# Ethernet1.net
KiCad netlist of a schematic drawn in Altium Designer
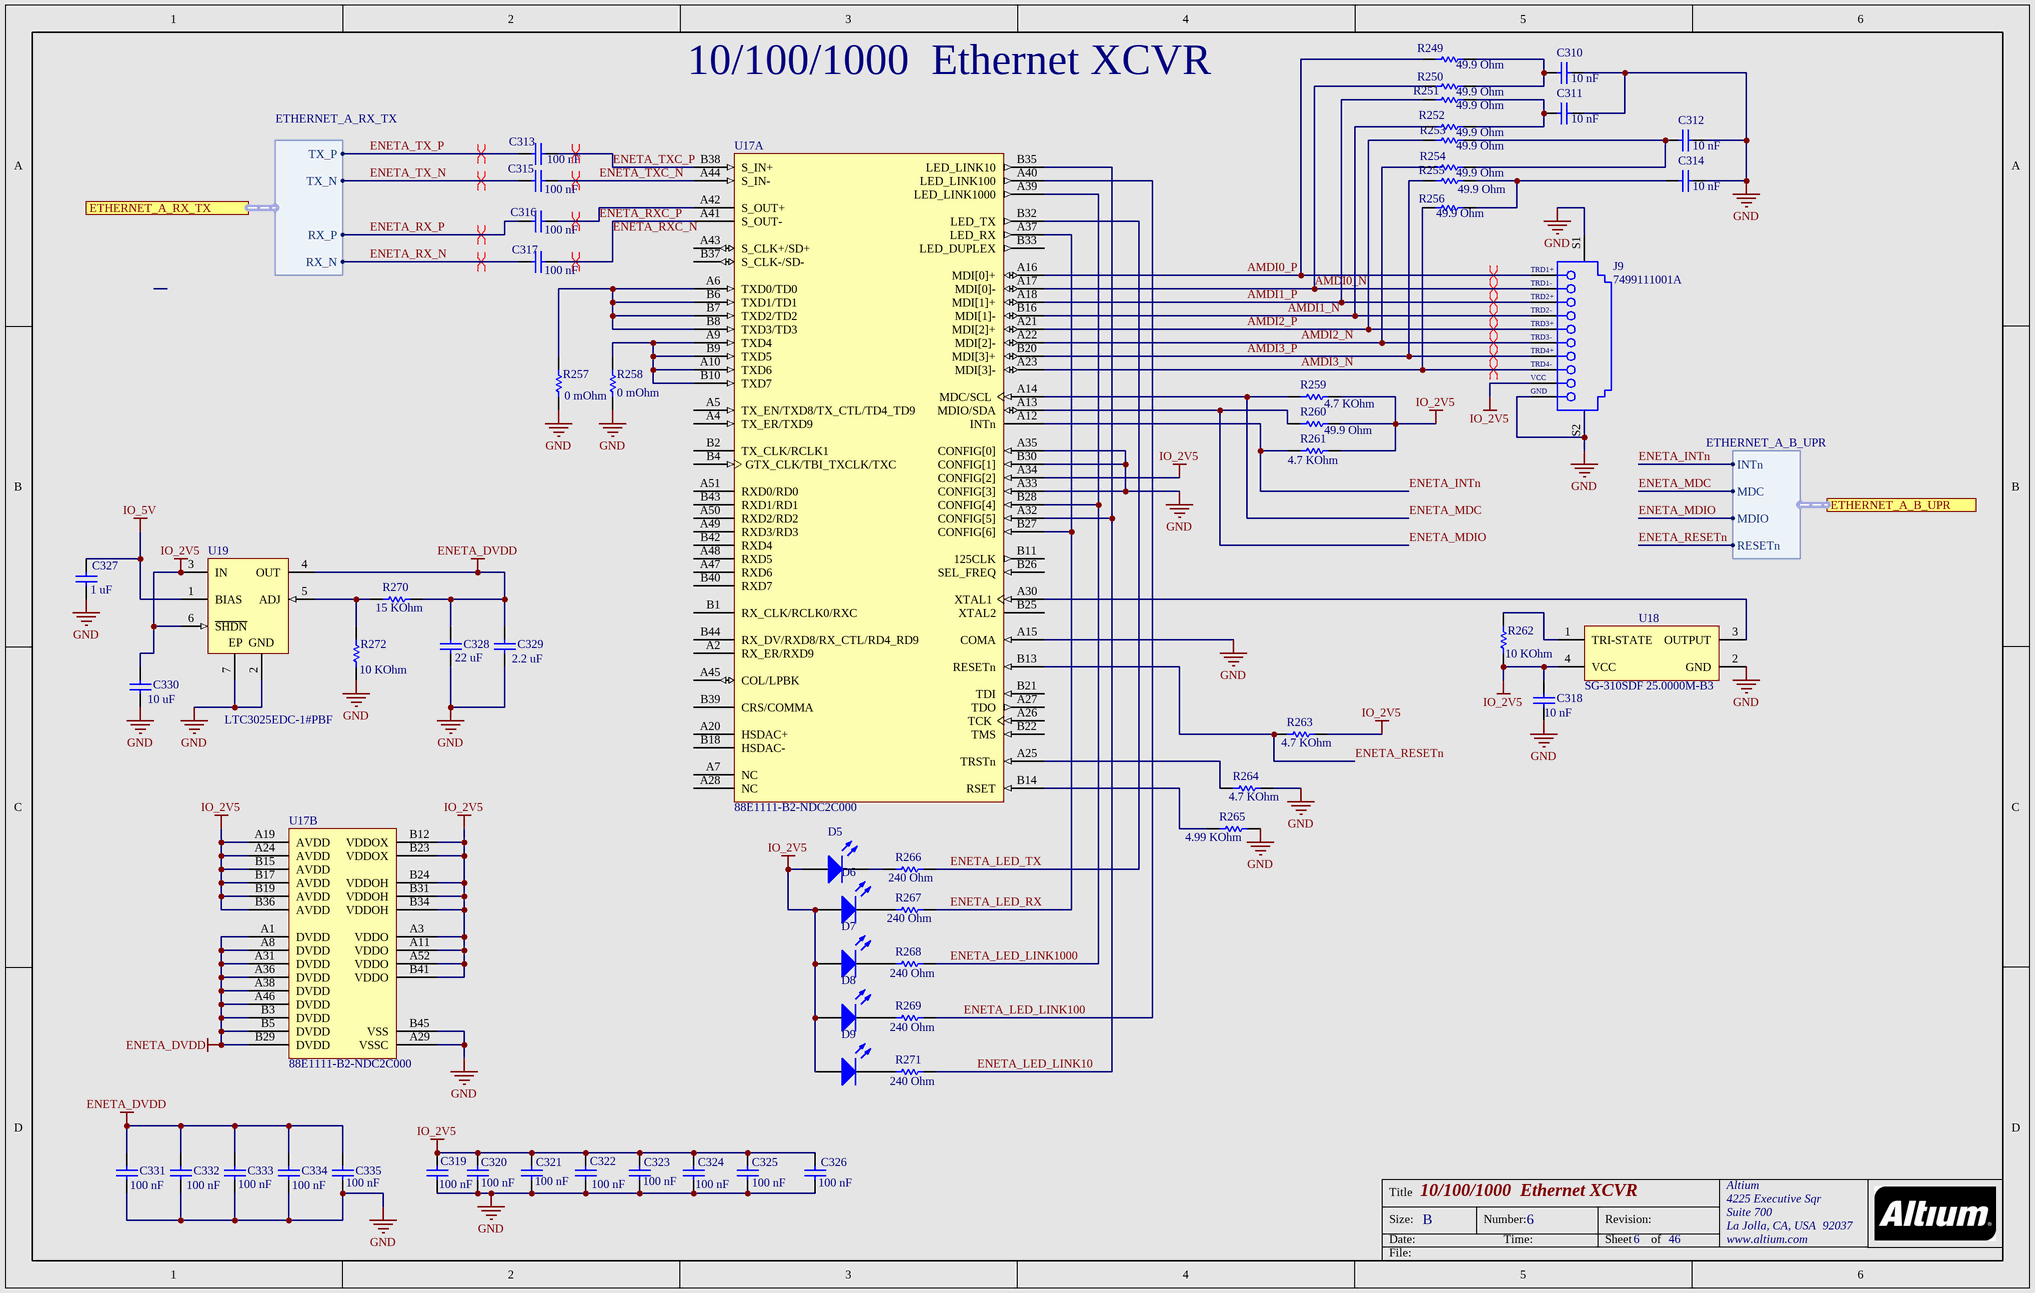
[diagram p0: Ethernet1.SchDoc]

(export (version "E")
  (design (tool "Eeschema 10.0.6"))
  (components
    (comp (ref "C310")
      (value "GRM155R71H103KA88D")
      (footprint "CAPC1005X55X25ML05T10")
      (description "Chip Capacitor, 10 nF, +/- 10%, 50 V, -55 to 125 degC, 0402 (1005 Metric), RoHS, Tape and Reel")
      (fields
        (field (name "TOLERANCE") "10%")
        (field (name "CAPACITANCE") "10 nF")
        (field (name "MANUFACTURER") "Basic Passives")
      )
      (libsource (lib "Altium Content Vault") (part "CAP-NP-2"))
    )
    (comp (ref "C311")
      (value "GRM155R71H103KA88D")
      (footprint "CAPC1005X55X25ML05T10")
      (description "Chip Capacitor, 10 nF, +/- 10%, 50 V, -55 to 125 degC, 0402 (1005 Metric), RoHS, Tape and Reel")
      (fields
        (field (name "TOLERANCE") "10%")
        (field (name "CAPACITANCE") "10 nF")
        (field (name "MANUFACTURER") "Basic Passives")
      )
      (libsource (lib "Altium Content Vault") (part "CAP-NP-2"))
    )
    (comp (ref "C312")
      (value "GRM155R71H103KA88D")
      (footprint "CAPC1005X55X25ML05T10")
      (description "Chip Capacitor, 10 nF, +/- 10%, 50 V, -55 to 125 degC, 0402 (1005 Metric), RoHS, Tape and Reel")
      (fields
        (field (name "TOLERANCE") "10%")
        (field (name "CAPACITANCE") "10 nF")
        (field (name "MANUFACTURER") "Basic Passives")
      )
      (libsource (lib "Altium Content Vault") (part "CAP-NP-2"))
    )
    (comp (ref "C313")
      (value "C1005X7R1E104M")
      (footprint "CAPC1005X55X10LL05")
      (description "Chip Capacitor, 0.1 uF, +/- 20%, 25 V, -55 to 125 degC, 0402 (1005 Metric), RoHS, Tape and Reel")
      (fields (field (name "TOLERANCE") "20%") (field (name "CAPACITANCE") "100 nF"))
      (libsource (lib "Altium Content Vault") (part "CAP-NP-2"))
    )
    (comp (ref "C314")
      (value "GRM155R71H103KA88D")
      (footprint "CAPC1005X55X25ML05T10")
      (description "Chip Capacitor, 10 nF, +/- 10%, 50 V, -55 to 125 degC, 0402 (1005 Metric), RoHS, Tape and Reel")
      (fields
        (field (name "TOLERANCE") "10%")
        (field (name "CAPACITANCE") "10 nF")
        (field (name "MANUFACTURER") "Basic Passives")
      )
      (libsource (lib "Altium Content Vault") (part "CAP-NP-2"))
    )
    (comp (ref "C315")
      (value "C1005X7R1E104M")
      (footprint "CAPC1005X55X10LL05")
      (description "Chip Capacitor, 0.1 uF, +/- 20%, 25 V, -55 to 125 degC, 0402 (1005 Metric), RoHS, Tape and Reel")
      (fields (field (name "TOLERANCE") "20%") (field (name "CAPACITANCE") "100 nF"))
      (libsource (lib "Altium Content Vault") (part "CAP-NP-2"))
    )
    (comp (ref "C316")
      (value "C1005X7R1E104M")
      (footprint "CAPC1005X55X10LL05")
      (description "Chip Capacitor, 0.1 uF, +/- 20%, 25 V, -55 to 125 degC, 0402 (1005 Metric), RoHS, Tape and Reel")
      (fields (field (name "TOLERANCE") "20%") (field (name "CAPACITANCE") "100 nF"))
      (libsource (lib "Altium Content Vault") (part "CAP-NP-2"))
    )
    (comp (ref "C317")
      (value "C1005X7R1E104M")
      (footprint "CAPC1005X55X10LL05")
      (description "Chip Capacitor, 0.1 uF, +/- 20%, 25 V, -55 to 125 degC, 0402 (1005 Metric), RoHS, Tape and Reel")
      (fields (field (name "TOLERANCE") "20%") (field (name "CAPACITANCE") "100 nF"))
      (libsource (lib "Altium Content Vault") (part "CAP-NP-2"))
    )
    (comp (ref "C318")
      (value "GRM155R71H103KA88D")
      (footprint "CAPC1005X55X25ML05T10")
      (description "Chip Capacitor, 10 nF, +/- 10%, 50 V, -55 to 125 degC, 0402 (1005 Metric), RoHS, Tape and Reel")
      (fields
        (field (name "TOLERANCE") "10%")
        (field (name "CAPACITANCE") "10 nF")
        (field (name "MANUFACTURER") "Basic Passives")
      )
      (libsource (lib "Altium Content Vault") (part "CAP-NP-2"))
    )
    (comp (ref "C319")
      (value "C1005X7R1E104M")
      (footprint "CAPC1005X55X10LL05")
      (description "Chip Capacitor, 0.1 uF, +/- 20%, 25 V, -55 to 125 degC, 0402 (1005 Metric), RoHS, Tape and Reel")
      (fields (field (name "TOLERANCE") "20%") (field (name "CAPACITANCE") "100 nF"))
      (libsource (lib "Altium Content Vault") (part "CAP-NP-2"))
    )
    (comp (ref "C320")
      (value "C1005X7R1E104M")
      (footprint "CAPC1005X55X10LL05")
      (description "Chip Capacitor, 0.1 uF, +/- 20%, 25 V, -55 to 125 degC, 0402 (1005 Metric), RoHS, Tape and Reel")
      (fields (field (name "TOLERANCE") "20%") (field (name "CAPACITANCE") "100 nF"))
      (libsource (lib "Altium Content Vault") (part "CAP-NP-2"))
    )
    (comp (ref "C321")
      (value "C1005X7R1E104M")
      (footprint "CAPC1005X55X10LL05")
      (description "Chip Capacitor, 0.1 uF, +/- 20%, 25 V, -55 to 125 degC, 0402 (1005 Metric), RoHS, Tape and Reel")
      (fields (field (name "TOLERANCE") "20%") (field (name "CAPACITANCE") "100 nF"))
      (libsource (lib "Altium Content Vault") (part "CAP-NP-2"))
    )
    (comp (ref "C322")
      (value "C1005X7R1E104M")
      (footprint "CAPC1005X55X10LL05")
      (description "Chip Capacitor, 0.1 uF, +/- 20%, 25 V, -55 to 125 degC, 0402 (1005 Metric), RoHS, Tape and Reel")
      (fields (field (name "TOLERANCE") "20%") (field (name "CAPACITANCE") "100 nF"))
      (libsource (lib "Altium Content Vault") (part "CAP-NP-2"))
    )
    (comp (ref "C323")
      (value "C1005X7R1E104M")
      (footprint "CAPC1005X55X10LL05")
      (description "Chip Capacitor, 0.1 uF, +/- 20%, 25 V, -55 to 125 degC, 0402 (1005 Metric), RoHS, Tape and Reel")
      (fields (field (name "TOLERANCE") "20%") (field (name "CAPACITANCE") "100 nF"))
      (libsource (lib "Altium Content Vault") (part "CAP-NP-2"))
    )
    (comp (ref "C324")
      (value "C1005X7R1E104M")
      (footprint "CAPC1005X55X10LL05")
      (description "Chip Capacitor, 0.1 uF, +/- 20%, 25 V, -55 to 125 degC, 0402 (1005 Metric), RoHS, Tape and Reel")
      (fields (field (name "TOLERANCE") "20%") (field (name "CAPACITANCE") "100 nF"))
      (libsource (lib "Altium Content Vault") (part "CAP-NP-2"))
    )
    (comp (ref "C325")
      (value "C1005X7R1E104M")
      (footprint "CAPC1005X55X10LL05")
      (description "Chip Capacitor, 0.1 uF, +/- 20%, 25 V, -55 to 125 degC, 0402 (1005 Metric), RoHS, Tape and Reel")
      (fields (field (name "TOLERANCE") "20%") (field (name "CAPACITANCE") "100 nF"))
      (libsource (lib "Altium Content Vault") (part "CAP-NP-2"))
    )
    (comp (ref "C326")
      (value "C1005X7R1E104M")
      (footprint "CAPC1005X55X10LL05")
      (description "Chip Capacitor, 0.1 uF, +/- 20%, 25 V, -55 to 125 degC, 0402 (1005 Metric), RoHS, Tape and Reel")
      (fields (field (name "TOLERANCE") "20%") (field (name "CAPACITANCE") "100 nF"))
      (libsource (lib "Altium Content Vault") (part "CAP-NP-2"))
    )
    (comp (ref "C327")
      (value "CGB2A1X5R1E105K033BC")
      (footprint "CAPC1005X33X10LL5")
      (description "Chip Capacitor, 1 uF, +/- 10%, 25 V, -55 to 85 degC, 0402 (1005 Metric), RoHS, Tape and Reel")
      (fields (field (name "CAPACITANCE") "1 uF") (field (name "TOLERANCE") "10%"))
      (libsource (lib "") (part "CAP-NP-2_1"))
    )
    (comp (ref "C328")
      (value "GRM31CR61E226KE15L")
      (footprint "CAPC3216X180X55ML20T25")
      (description "Chip Capacitor, 22 uF, +/- 10%, 25 V, -55 to 85 degC, 1206 (3216 Metric), RoHS, Tape and Reel")
      (fields (field (name "TOLERANCE") "10%") (field (name "CAPACITANCE") "22 uF"))
      (libsource (lib "Altium Content Vault") (part "CAP-NP-2"))
    )
    (comp (ref "C329")
      (value "GRM188R61A225KE34x")
      (footprint "CAPC1608X90X35ML10T15")
      (description "Chip Capacitor, 2.2 uF, +/- 10%, 10 V, -55 to 85 degC, 0603 (1608 Metric), RoHS, Tape and Reel")
      (fields (field (name "TOLERANCE") "10%") (field (name "CAPACITANCE") "2.2 uF"))
      (libsource (lib "Altium Content Vault") (part "CMP-1662-00016-2"))
    )
    (comp (ref "C330")
      (value "C2012X5R1C106K085AC")
      (footprint "CAPC2013X100X20NL20")
      (description "Chip Capacitor, 10 uF, +/- 10%, 16 V, -55 to 85 degC, 0805 (2012 Metric), RoHS, Tape and Reel")
      (fields (field (name "TOLERANCE") "10%") (field (name "CAPACITANCE") "10 uF"))
      (libsource (lib "Altium Content Vault") (part "CMP-1663-00007-1"))
    )
    (comp (ref "C331")
      (value "C1005X7R1E104M")
      (footprint "CAPC1005X55X10LL05")
      (description "Chip Capacitor, 0.1 uF, +/- 20%, 25 V, -55 to 125 degC, 0402 (1005 Metric), RoHS, Tape and Reel")
      (fields (field (name "TOLERANCE") "20%") (field (name "CAPACITANCE") "100 nF"))
      (libsource (lib "Altium Content Vault") (part "CAP-NP-2"))
    )
    (comp (ref "C332")
      (value "C1005X7R1E104M")
      (footprint "CAPC1005X55X10LL05")
      (description "Chip Capacitor, 0.1 uF, +/- 20%, 25 V, -55 to 125 degC, 0402 (1005 Metric), RoHS, Tape and Reel")
      (fields (field (name "TOLERANCE") "20%") (field (name "CAPACITANCE") "100 nF"))
      (libsource (lib "Altium Content Vault") (part "CAP-NP-2"))
    )
    (comp (ref "C333")
      (value "C1005X7R1E104M")
      (footprint "CAPC1005X55X10LL05")
      (description "Chip Capacitor, 0.1 uF, +/- 20%, 25 V, -55 to 125 degC, 0402 (1005 Metric), RoHS, Tape and Reel")
      (fields (field (name "TOLERANCE") "20%") (field (name "CAPACITANCE") "100 nF"))
      (libsource (lib "Altium Content Vault") (part "CAP-NP-2"))
    )
    (comp (ref "C334")
      (value "C1005X7R1E104M")
      (footprint "CAPC1005X55X10LL05")
      (description "Chip Capacitor, 0.1 uF, +/- 20%, 25 V, -55 to 125 degC, 0402 (1005 Metric), RoHS, Tape and Reel")
      (fields (field (name "TOLERANCE") "20%") (field (name "CAPACITANCE") "100 nF"))
      (libsource (lib "Altium Content Vault") (part "CAP-NP-2"))
    )
    (comp (ref "C335")
      (value "C1005X7R1E104M")
      (footprint "CAPC1005X55X10LL05")
      (description "Chip Capacitor, 0.1 uF, +/- 20%, 25 V, -55 to 125 degC, 0402 (1005 Metric), RoHS, Tape and Reel")
      (fields (field (name "TOLERANCE") "20%") (field (name "CAPACITANCE") "100 nF"))
      (libsource (lib "Altium Content Vault") (part "CAP-NP-2"))
    )
    (comp (ref "D5")
      (value "150060VS75000")
      (footprint "0603_A")
      (description "SMD mono-color Chip LED, WL-SMCW, Bright Green")
      (fields (field (name "MANUFACTURER") "Wuerth Elektronik"))
      (libsource (lib "Altium Content Vault") (part "CMP-1426-00006-1"))
    )
    (comp (ref "D6")
      (value "150060VS75000")
      (footprint "0603_A")
      (description "SMD mono-color Chip LED, WL-SMCW, Bright Green")
      (fields (field (name "MANUFACTURER") "Wuerth Elektronik"))
      (libsource (lib "Altium Content Vault") (part "CMP-1426-00006-1"))
    )
    (comp (ref "D7")
      (value "150060VS75000")
      (footprint "0603_A")
      (description "SMD mono-color Chip LED, WL-SMCW, Bright Green")
      (fields (field (name "MANUFACTURER") "Wuerth Elektronik"))
      (libsource (lib "Altium Content Vault") (part "CMP-1426-00006-1"))
    )
    (comp (ref "D8")
      (value "150060VS75000")
      (footprint "0603_A")
      (description "SMD mono-color Chip LED, WL-SMCW, Bright Green")
      (fields (field (name "MANUFACTURER") "Wuerth Elektronik"))
      (libsource (lib "Altium Content Vault") (part "CMP-1426-00006-1"))
    )
    (comp (ref "D9")
      (value "150060VS75000")
      (footprint "0603_A")
      (description "SMD mono-color Chip LED, WL-SMCW, Bright Green")
      (fields (field (name "MANUFACTURER") "Wuerth Elektronik"))
      (libsource (lib "Altium Content Vault") (part "CMP-1426-00006-1"))
    )
    (comp (ref "J9")
      (value "7499111001A")
      (footprint "WE-7499111001A_V")
      (description "RJ45 LAN Transformer, Modular JACK, 0 to 70 degC, 10-Pin THD, RoHS, Tube")
      (libsource (lib "Altium Content Vault") (part "RJ45-10-2SHLD_A"))
    )
    (comp (ref "R249")
      (value "NRC04F49R9TRF")
      (footprint "RESC1005X35X25NL8T10")
      (description "Chip Resistor, 49.9 Ohm, +/- 1%, 0.06 W, -55 to 155 degC, 0402 (1005 Metric), RoHS, Tape and Reel")
      (fields (field (name "TOLERANCE") "1%") (field (name "RESISTANCE") "49.9 Ohm"))
      (libsource (lib "Altium Content Vault") (part "RES-2"))
    )
    (comp (ref "R250")
      (value "NRC04F49R9TRF")
      (footprint "RESC1005X35X25NL8T10")
      (description "Chip Resistor, 49.9 Ohm, +/- 1%, 0.06 W, -55 to 155 degC, 0402 (1005 Metric), RoHS, Tape and Reel")
      (fields (field (name "TOLERANCE") "1%") (field (name "RESISTANCE") "49.9 Ohm"))
      (libsource (lib "Altium Content Vault") (part "CMP-1599-00001-2"))
    )
    (comp (ref "R251")
      (value "NRC04F49R9TRF")
      (footprint "RESC1005X35X25NL8T10")
      (description "Chip Resistor, 49.9 Ohm, +/- 1%, 0.06 W, -55 to 155 degC, 0402 (1005 Metric), RoHS, Tape and Reel")
      (fields (field (name "TOLERANCE") "1%") (field (name "RESISTANCE") "49.9 Ohm"))
      (libsource (lib "Altium Content Vault") (part "CMP-1599-00001-2"))
    )
    (comp (ref "R252")
      (value "NRC04F49R9TRF")
      (footprint "RESC1005X35X25NL8T10")
      (description "Chip Resistor, 49.9 Ohm, +/- 1%, 0.06 W, -55 to 155 degC, 0402 (1005 Metric), RoHS, Tape and Reel")
      (fields (field (name "TOLERANCE") "1%") (field (name "RESISTANCE") "49.9 Ohm"))
      (libsource (lib "Altium Content Vault") (part "RES-2"))
    )
    (comp (ref "R253")
      (value "NRC04F49R9TRF")
      (footprint "RESC1005X35X25NL8T10")
      (description "Chip Resistor, 49.9 Ohm, +/- 1%, 0.06 W, -55 to 155 degC, 0402 (1005 Metric), RoHS, Tape and Reel")
      (fields (field (name "TOLERANCE") "1%") (field (name "RESISTANCE") "49.9 Ohm"))
      (libsource (lib "Altium Content Vault") (part "CMP-1599-00001-2"))
    )
    (comp (ref "R254")
      (value "NRC04F49R9TRF")
      (footprint "RESC1005X35X25NL8T10")
      (description "Chip Resistor, 49.9 Ohm, +/- 1%, 0.06 W, -55 to 155 degC, 0402 (1005 Metric), RoHS, Tape and Reel")
      (fields (field (name "TOLERANCE") "1%") (field (name "RESISTANCE") "49.9 Ohm"))
      (libsource (lib "Altium Content Vault") (part "CMP-1599-00001-2"))
    )
    (comp (ref "R255")
      (value "NRC04F49R9TRF")
      (footprint "RESC1005X35X25NL8T10")
      (description "Chip Resistor, 49.9 Ohm, +/- 1%, 0.06 W, -55 to 155 degC, 0402 (1005 Metric), RoHS, Tape and Reel")
      (fields (field (name "TOLERANCE") "1%") (field (name "RESISTANCE") "49.9 Ohm"))
      (libsource (lib "Altium Content Vault") (part "RES-2"))
    )
    (comp (ref "R256")
      (value "NRC04F49R9TRF")
      (footprint "RESC1005X35X25NL8T10")
      (description "Chip Resistor, 49.9 Ohm, +/- 1%, 0.06 W, -55 to 155 degC, 0402 (1005 Metric), RoHS, Tape and Reel")
      (fields (field (name "TOLERANCE") "1%") (field (name "RESISTANCE") "49.9 Ohm"))
      (libsource (lib "Altium Content Vault") (part "CMP-1599-00001-2"))
    )
    (comp (ref "R257")
      (value "ERJ-2GE0R00X")
      (footprint "RESC1005X40X25ML05T05")
      (description "Chip Resistor, 0 mOhm, +/- 5%, 100 mW, -55 to 155 degC, 0402 (1005 Metric), RoHS, Tape and Reel")
      (fields
        (field (name "TOLERANCE") "5%")
        (field (name "RESISTANCE") "0 mOhm")
        (field (name "MANUFACTURER") "Basic Passives")
      )
      (libsource (lib "Altium Content Vault") (part "RES-2"))
    )
    (comp (ref "R258")
      (value "ERJ-2GE0R00X")
      (footprint "RESC1005X40X25ML05T05")
      (description "Chip Resistor, 0 mOhm, +/- 5%, 100 mW, -55 to 155 degC, 0402 (1005 Metric), RoHS, Tape and Reel")
      (fields
        (field (name "TOLERANCE") "5%")
        (field (name "RESISTANCE") "0 mOhm")
        (field (name "MANUFACTURER") "Basic Passives")
      )
      (libsource (lib "Altium Content Vault") (part "RES-2"))
    )
    (comp (ref "R259")
      (value "ERJ-2RKF4701X")
      (footprint "RESC1005X40X25LL05T05")
      (description "Chip Resistor, 4.7 KOhm, +/- 1%, 0.1 W, -55 to 155 degC, 0402 (1005 Metric), RoHS, Tape and Reel")
      (fields (field (name "TOLERANCE") "1%") (field (name "RESISTANCE") "4.7 KOhm"))
      (libsource (lib "Altium Content Vault") (part "RES-2"))
    )
    (comp (ref "R260")
      (value "NRC04F49R9TRF")
      (footprint "RESC1005X35X25NL8T10")
      (description "Chip Resistor, 49.9 Ohm, +/- 1%, 0.06 W, -55 to 155 degC, 0402 (1005 Metric), RoHS, Tape and Reel")
      (fields (field (name "TOLERANCE") "1%") (field (name "RESISTANCE") "49.9 Ohm"))
      (libsource (lib "Altium Content Vault") (part "RES-2"))
    )
    (comp (ref "R261")
      (value "ERJ-2RKF4701X")
      (footprint "RESC1005X40X25LL05T05")
      (description "Chip Resistor, 4.7 KOhm, +/- 1%, 0.1 W, -55 to 155 degC, 0402 (1005 Metric), RoHS, Tape and Reel")
      (fields (field (name "TOLERANCE") "1%") (field (name "RESISTANCE") "4.7 KOhm"))
      (libsource (lib "Altium Content Vault") (part "RES-2"))
    )
    (comp (ref "R262")
      (value "ERJ-2RKF1002X")
      (footprint "RESC1005X40X25NL05T05")
      (description "Chip Resistor, 10 KOhm, +/- 1%, 100 mW, -55 to 155 degC, 0402 (1005 Metric), RoHS, Tape and Reel")
      (fields
        (field (name "TOLERANCE") "1%")
        (field (name "RESISTANCE") "10 KOhm")
        (field (name "MANUFACTURER") "Basic Passives")
      )
      (libsource (lib "Altium Content Vault") (part "RES-2"))
    )
    (comp (ref "R263")
      (value "ERJ-2RKF4701X")
      (footprint "RESC1005X40X25LL05T05")
      (description "Chip Resistor, 4.7 KOhm, +/- 1%, 0.1 W, -55 to 155 degC, 0402 (1005 Metric), RoHS, Tape and Reel")
      (fields (field (name "TOLERANCE") "1%") (field (name "RESISTANCE") "4.7 KOhm"))
      (libsource (lib "Altium Content Vault") (part "RES-2"))
    )
    (comp (ref "R264")
      (value "ERJ-2RKF4701X")
      (footprint "RESC1005X40X25LL05T05")
      (description "Chip Resistor, 4.7 KOhm, +/- 1%, 0.1 W, -55 to 155 degC, 0402 (1005 Metric), RoHS, Tape and Reel")
      (fields (field (name "TOLERANCE") "1%") (field (name "RESISTANCE") "4.7 KOhm"))
      (libsource (lib "Altium Content Vault") (part "RES-2"))
    )
    (comp (ref "R265")
      (value "ERJ-2RKF4991X")
      (footprint "RESC1005X40X25NL05T05")
      (description "Chip Resistor, 4.99 KOhm, +/- 1%, 100 mW, -55 to 155 degC, 0402 (1005 Metric), RoHS, Tape and Reel")
      (fields
        (field (name "TOLERANCE") "1%")
        (field (name "RESISTANCE") "4.99 KOhm")
        (field (name "MANUFACTURER") "Basic Passives")
      )
      (libsource (lib "Altium Content Vault") (part "RES-2"))
    )
    (comp (ref "R266")
      (value "ERJ-2RKF2400X")
      (footprint "RESC1005X40X25NL05T05")
      (description "Chip Resistor, 240 Ohm, +/- 1%, 100 mW, -55 to 155 degC, 0402 (1005 Metric), RoHS, Tape and Reel")
      (fields (field (name "TOLERANCE") "1%") (field (name "RESISTANCE") "240 Ohm"))
      (libsource (lib "Altium Content Vault") (part "RES-2"))
    )
    (comp (ref "R267")
      (value "ERJ-2RKF2400X")
      (footprint "RESC1005X40X25NL05T05")
      (description "Chip Resistor, 240 Ohm, +/- 1%, 100 mW, -55 to 155 degC, 0402 (1005 Metric), RoHS, Tape and Reel")
      (fields (field (name "TOLERANCE") "1%") (field (name "RESISTANCE") "240 Ohm"))
      (libsource (lib "Altium Content Vault") (part "RES-2"))
    )
    (comp (ref "R268")
      (value "ERJ-2RKF2400X")
      (footprint "RESC1005X40X25NL05T05")
      (description "Chip Resistor, 240 Ohm, +/- 1%, 100 mW, -55 to 155 degC, 0402 (1005 Metric), RoHS, Tape and Reel")
      (fields (field (name "TOLERANCE") "1%") (field (name "RESISTANCE") "240 Ohm"))
      (libsource (lib "Altium Content Vault") (part "RES-2"))
    )
    (comp (ref "R269")
      (value "ERJ-2RKF2400X")
      (footprint "RESC1005X40X25NL05T05")
      (description "Chip Resistor, 240 Ohm, +/- 1%, 100 mW, -55 to 155 degC, 0402 (1005 Metric), RoHS, Tape and Reel")
      (fields (field (name "TOLERANCE") "1%") (field (name "RESISTANCE") "240 Ohm"))
      (libsource (lib "Altium Content Vault") (part "RES-2"))
    )
    (comp (ref "R270")
      (value "ERJ-2RKF1502X")
      (footprint "RESC1005X40X25ML05T05")
      (description "Chip Resistor, 15 KOhm, +/- 1%, 100 mW, -55 to 155 degC, 0402 (1005 Metric), RoHS, Tape and Reel")
      (fields
        (field (name "RESISTANCE") "15 KOhm")
        (field (name "TOLERANCE") "1%")
        (field (name "MANUFACTURER") "Basic Passives")
      )
      (libsource (lib "Altium Content Vault") (part "RES-2"))
    )
    (comp (ref "R271")
      (value "ERJ-2RKF2400X")
      (footprint "RESC1005X40X25NL05T05")
      (description "Chip Resistor, 240 Ohm, +/- 1%, 100 mW, -55 to 155 degC, 0402 (1005 Metric), RoHS, Tape and Reel")
      (fields (field (name "TOLERANCE") "1%") (field (name "RESISTANCE") "240 Ohm"))
      (libsource (lib "Altium Content Vault") (part "RES-2"))
    )
    (comp (ref "R272")
      (value "ERJ-2RKF1002X")
      (footprint "RESC1005X40X25NL05T05")
      (description "Chip Resistor, 10 KOhm, +/- 1%, 100 mW, -55 to 155 degC, 0402 (1005 Metric), RoHS, Tape and Reel")
      (fields
        (field (name "TOLERANCE") "1%")
        (field (name "RESISTANCE") "10 KOhm")
        (field (name "MANUFACTURER") "Basic Passives")
      )
      (libsource (lib "Altium Content Vault") (part "RES-2"))
    )
    (comp (ref "U17")
      (value "88E1111-B2-NDC2C000")
      (footprint "MARV-NDC96")
      (description "Integrated 10/100/1000 Ultra Gigabit Ethernet Transceiver, Commercial Grade, 96-Pin QFN, RoHS")
      (libsource (lib "Altium Content Vault") (part "MARV-88E1111-NDC96"))
    )
    (comp (ref "U18")
      (value "SG-310SDF 25.0000M-B3")
      (footprint "EPSON-SG-310-4_V")
      (description "Crystal Oscillator (SPXO), 2.5 V, 25 MHz, -20 to 70 degC, 4-Pin SMD, RoHS, Tape and Reel")
      (libsource (lib "Altium Content Vault") (part "XTAL-1-3-4_B"))
    )
    (comp (ref "U19")
      (value "LTC3025EDC-1#PBF")
      (footprint "LT-DC6-6_V")
      (fields (field (name "MANUFACTURER") "Linear Technology"))
      (libsource (lib "Altium Content Vault") (part "LT-LTC302-DC6-6"))
    )
  )
  (nets
    (net (code "3") (name "/AMDI0_N") (class "Default")
      (node (ref "J9") (pin "2") (pinfunction "TRD1-_2") (pintype "passive"))
      (node (ref "R250") (pin "1") (pinfunction "1_1") (pintype "passive"))
      (node (ref "U17") (pin "A17") (pinfunction "MDI[0]-_A17") (pintype "bidirectional"))
    )
    (net (code "4") (name "/AMDI0_P") (class "Default")
      (node (ref "J9") (pin "1") (pinfunction "TRD1+_1") (pintype "passive"))
      (node (ref "R249") (pin "1") (pinfunction "1_1") (pintype "passive"))
      (node (ref "U17") (pin "A16") (pinfunction "MDI[0]+_A16") (pintype "bidirectional"))
    )
    (net (code "5") (name "/AMDI1_N") (class "Default")
      (node (ref "J9") (pin "4") (pinfunction "TRD2-_4") (pintype "passive"))
      (node (ref "R252") (pin "1") (pinfunction "1_1") (pintype "passive"))
      (node (ref "U17") (pin "B16") (pinfunction "MDI[1]-_B16") (pintype "bidirectional"))
    )
    (net (code "6") (name "/AMDI1_P") (class "Default")
      (node (ref "J9") (pin "3") (pinfunction "TRD2+_3") (pintype "passive"))
      (node (ref "R251") (pin "1") (pinfunction "1_1") (pintype "passive"))
      (node (ref "U17") (pin "A18") (pinfunction "MDI[1]+_A18") (pintype "bidirectional"))
    )
    (net (code "7") (name "/AMDI2_N") (class "Default")
      (node (ref "J9") (pin "6") (pinfunction "TRD3-_6") (pintype "passive"))
      (node (ref "R254") (pin "1") (pinfunction "1_1") (pintype "passive"))
      (node (ref "U17") (pin "A22") (pinfunction "MDI[2]-_A22") (pintype "bidirectional"))
    )
    (net (code "8") (name "/AMDI2_P") (class "Default")
      (node (ref "J9") (pin "5") (pinfunction "TRD3+_5") (pintype "passive"))
      (node (ref "R253") (pin "1") (pinfunction "1_1") (pintype "passive"))
      (node (ref "U17") (pin "A21") (pinfunction "MDI[2]+_A21") (pintype "bidirectional"))
    )
    (net (code "9") (name "/AMDI3_N") (class "Default")
      (node (ref "J9") (pin "8") (pinfunction "TRD4-_8") (pintype "passive"))
      (node (ref "R256") (pin "1") (pinfunction "1_1") (pintype "passive"))
      (node (ref "U17") (pin "A23") (pinfunction "MDI[3]-_A23") (pintype "bidirectional"))
    )
    (net (code "10") (name "/AMDI3_P") (class "Default")
      (node (ref "J9") (pin "7") (pinfunction "TRD4+_7") (pintype "passive"))
      (node (ref "R255") (pin "1") (pinfunction "1_1") (pintype "passive"))
      (node (ref "U17") (pin "B20") (pinfunction "MDI[3]+_B20") (pintype "bidirectional"))
    )
    (net (code "11") (name "/ENETA_INTn") (class "Default")
      (node (ref "R261") (pin "1") (pinfunction "1_1") (pintype "passive"))
      (node (ref "U17") (pin "A12") (pinfunction "INTn_A12") (pintype "passive"))
    )
    (net (code "12") (name "/ENETA_LED_LINK10") (class "Default")
      (node (ref "R271") (pin "2") (pinfunction "2_2") (pintype "passive"))
      (node (ref "U17") (pin "A32") (pinfunction "CONFIG[5]_A32") (pintype "input"))
      (node (ref "U17") (pin "B35") (pinfunction "LED_LINK10_B35") (pintype "output"))
    )
    (net (code "13") (name "/ENETA_LED_LINK100") (class "Default")
      (node (ref "R269") (pin "2") (pinfunction "2_2") (pintype "passive"))
      (node (ref "U17") (pin "A40") (pinfunction "LED_LINK100_A40") (pintype "output"))
    )
    (net (code "14") (name "/ENETA_LED_LINK1000") (class "Default")
      (node (ref "R268") (pin "2") (pinfunction "2_2") (pintype "passive"))
      (node (ref "U17") (pin "A39") (pinfunction "LED_LINK1000_A39") (pintype "output"))
      (node (ref "U17") (pin "B28") (pinfunction "CONFIG[4]_B28") (pintype "input"))
    )
    (net (code "15") (name "/ENETA_LED_RX") (class "Default")
      (node (ref "R267") (pin "2") (pinfunction "2_2") (pintype "passive"))
      (node (ref "U17") (pin "A37") (pinfunction "LED_RX_A37") (pintype "output"))
      (node (ref "U17") (pin "B27") (pinfunction "CONFIG[6]_B27") (pintype "input"))
    )
    (net (code "16") (name "/ENETA_LED_TX") (class "Default")
      (node (ref "R266") (pin "2") (pinfunction "2_2") (pintype "passive"))
      (node (ref "U17") (pin "B32") (pinfunction "LED_TX_B32") (pintype "output"))
    )
    (net (code "17") (name "/ENETA_MDC") (class "Default")
      (node (ref "R259") (pin "1") (pinfunction "1_1") (pintype "passive"))
      (node (ref "U17") (pin "A14") (pinfunction "MDC/SCL_A14") (pintype "input"))
    )
    (net (code "18") (name "/ENETA_MDIO") (class "Default")
      (node (ref "R260") (pin "1") (pinfunction "1_1") (pintype "passive"))
      (node (ref "U17") (pin "A13") (pinfunction "MDIO/SDA_A13") (pintype "bidirectional"))
    )
    (net (code "19") (name "/ENETA_RESETn") (class "Default")
      (node (ref "R263") (pin "1") (pinfunction "1_1") (pintype "passive"))
      (node (ref "U17") (pin "B13") (pinfunction "RESETn_B13") (pintype "input"))
    )
    (net (code "20") (name "/ENETA_RXC_N") (class "Default")
      (node (ref "C317") (pin "2") (pinfunction "2_2") (pintype "passive"))
      (node (ref "U17") (pin "A41") (pinfunction "S_OUT-_A41") (pintype "tri_state"))
    )
    (net (code "21") (name "/ENETA_RXC_P") (class "Default")
      (node (ref "C316") (pin "2") (pinfunction "2_2") (pintype "passive"))
      (node (ref "U17") (pin "A42") (pinfunction "S_OUT+_A42") (pintype "tri_state"))
    )
    (net (code "22") (name "/ENETA_RX_N") (class "Default")
      (node (ref "C317") (pin "1") (pinfunction "1_1") (pintype "passive"))
    )
    (net (code "23") (name "/ENETA_RX_P") (class "Default")
      (node (ref "C316") (pin "1") (pinfunction "1_1") (pintype "passive"))
    )
    (net (code "24") (name "/ENETA_TXC_N") (class "Default")
      (node (ref "C315") (pin "2") (pinfunction "2_2") (pintype "passive"))
      (node (ref "U17") (pin "A44") (pinfunction "S_IN-_A44") (pintype "input"))
    )
    (net (code "25") (name "/ENETA_TXC_P") (class "Default")
      (node (ref "C313") (pin "2") (pinfunction "2_2") (pintype "passive"))
      (node (ref "U17") (pin "B38") (pinfunction "S_IN+_B38") (pintype "input"))
    )
    (net (code "26") (name "/ENETA_TX_N") (class "Default")
      (node (ref "C315") (pin "1") (pinfunction "1_1") (pintype "passive"))
    )
    (net (code "27") (name "/ENETA_TX_P") (class "Default")
      (node (ref "C313") (pin "1") (pinfunction "1_1") (pintype "passive"))
    )
    (net (code "30") (name "ENETA_DVDD") (class "Default")
      (node (ref "C328") (pin "2") (pinfunction "2_2") (pintype "passive"))
      (node (ref "C329") (pin "2") (pinfunction "2_2") (pintype "passive"))
      (node (ref "C331") (pin "2") (pinfunction "2_2") (pintype "passive"))
      (node (ref "C332") (pin "2") (pinfunction "2_2") (pintype "passive"))
      (node (ref "C333") (pin "2") (pinfunction "2_2") (pintype "passive"))
      (node (ref "C334") (pin "2") (pinfunction "2_2") (pintype "passive"))
      (node (ref "C335") (pin "2") (pinfunction "2_2") (pintype "passive"))
      (node (ref "R270") (pin "2") (pinfunction "2_2") (pintype "passive"))
      (node (ref "U17") (pin "A1") (pinfunction "DVDD_A1") (pintype "power_in"))
      (node (ref "U17") (pin "A31") (pinfunction "DVDD_A31") (pintype "power_in"))
      (node (ref "U17") (pin "A36") (pinfunction "DVDD_A36") (pintype "power_in"))
      (node (ref "U17") (pin "A38") (pinfunction "DVDD_A38") (pintype "power_in"))
      (node (ref "U17") (pin "A46") (pinfunction "DVDD_A46") (pintype "power_in"))
      (node (ref "U17") (pin "A8") (pinfunction "DVDD_A8") (pintype "power_in"))
      (node (ref "U17") (pin "B29") (pinfunction "DVDD_B29") (pintype "power_in"))
      (node (ref "U17") (pin "B3") (pinfunction "DVDD_B3") (pintype "power_in"))
      (node (ref "U17") (pin "B5") (pinfunction "DVDD_B5") (pintype "power_in"))
      (node (ref "U19") (pin "4") (pinfunction "OUT_4") (pintype "power_in"))
    )
    (net (code "31") (name "GND") (class "Default")
      (node (ref "C310") (pin "2") (pinfunction "2_2") (pintype "passive"))
      (node (ref "C311") (pin "2") (pinfunction "2_2") (pintype "passive"))
      (node (ref "C312") (pin "2") (pinfunction "2_2") (pintype "passive"))
      (node (ref "C314") (pin "2") (pinfunction "2_2") (pintype "passive"))
      (node (ref "C318") (pin "1") (pinfunction "1_1") (pintype "passive"))
      (node (ref "C319") (pin "1") (pinfunction "1_1") (pintype "passive"))
      (node (ref "C320") (pin "1") (pinfunction "1_1") (pintype "passive"))
      (node (ref "C321") (pin "1") (pinfunction "1_1") (pintype "passive"))
      (node (ref "C322") (pin "1") (pinfunction "1_1") (pintype "passive"))
      (node (ref "C323") (pin "1") (pinfunction "1_1") (pintype "passive"))
      (node (ref "C324") (pin "1") (pinfunction "1_1") (pintype "passive"))
      (node (ref "C325") (pin "1") (pinfunction "1_1") (pintype "passive"))
      (node (ref "C326") (pin "1") (pinfunction "1_1") (pintype "passive"))
      (node (ref "C327") (pin "1") (pinfunction "1_1") (pintype "passive"))
      (node (ref "C328") (pin "1") (pinfunction "1_1") (pintype "passive"))
      (node (ref "C329") (pin "1") (pinfunction "1_1") (pintype "passive"))
      (node (ref "C330") (pin "1") (pinfunction "1_1") (pintype "passive"))
      (node (ref "C331") (pin "1") (pinfunction "1_1") (pintype "passive"))
      (node (ref "C332") (pin "1") (pinfunction "1_1") (pintype "passive"))
      (node (ref "C333") (pin "1") (pinfunction "1_1") (pintype "passive"))
      (node (ref "C334") (pin "1") (pinfunction "1_1") (pintype "passive"))
      (node (ref "C335") (pin "1") (pinfunction "1_1") (pintype "passive"))
      (node (ref "J9") (pin "10") (pinfunction "GND_10") (pintype "power_in"))
      (node (ref "J9") (pin "S1") (pinfunction "SHLD_S1") (pintype "passive"))
      (node (ref "J9") (pin "S2") (pinfunction "SHLD_S2") (pintype "passive"))
      (node (ref "R257") (pin "1") (pinfunction "1_1") (pintype "passive"))
      (node (ref "R258") (pin "1") (pinfunction "1_1") (pintype "passive"))
      (node (ref "R264") (pin "2") (pinfunction "2_2") (pintype "passive"))
      (node (ref "R265") (pin "2") (pinfunction "2_2") (pintype "passive"))
      (node (ref "R272") (pin "1") (pinfunction "1_1") (pintype "passive"))
      (node (ref "U17") (pin "A15") (pinfunction "COMA_A15") (pintype "input"))
      (node (ref "U17") (pin "A29") (pinfunction "VSSC_A29") (pintype "power_in"))
      (node (ref "U17") (pin "A33") (pinfunction "CONFIG[3]_A33") (pintype "input"))
      (node (ref "U17") (pin "A35") (pinfunction "CONFIG[0]_A35") (pintype "input"))
      (node (ref "U17") (pin "B30") (pinfunction "CONFIG[1]_B30") (pintype "input"))
      (node (ref "U17") (pin "B45") (pinfunction "VSS_B45") (pintype "power_in"))
      (node (ref "U18") (pin "2") (pinfunction "GND_2") (pintype "power_in"))
      (node (ref "U19") (pin "2") (pinfunction "GND_2") (pintype "power_in"))
      (node (ref "U19") (pin "7") (pinfunction "EP_7") (pintype "power_in"))
    )
    (net (code "32") (name "IO_2V5") (class "Default")
      (node (ref "C318") (pin "2") (pinfunction "2_2") (pintype "passive"))
      (node (ref "C319") (pin "2") (pinfunction "2_2") (pintype "passive"))
      (node (ref "C320") (pin "2") (pinfunction "2_2") (pintype "passive"))
      (node (ref "C321") (pin "2") (pinfunction "2_2") (pintype "passive"))
      (node (ref "C322") (pin "2") (pinfunction "2_2") (pintype "passive"))
      (node (ref "C323") (pin "2") (pinfunction "2_2") (pintype "passive"))
      (node (ref "C324") (pin "2") (pinfunction "2_2") (pintype "passive"))
      (node (ref "C325") (pin "2") (pinfunction "2_2") (pintype "passive"))
      (node (ref "C326") (pin "2") (pinfunction "2_2") (pintype "passive"))
      (node (ref "C330") (pin "2") (pinfunction "2_2") (pintype "passive"))
      (node (ref "D5") (pin "2") (pinfunction "A_2") (pintype "passive"))
      (node (ref "D6") (pin "2") (pinfunction "A_2") (pintype "passive"))
      (node (ref "D7") (pin "2") (pinfunction "A_2") (pintype "passive"))
      (node (ref "D8") (pin "2") (pinfunction "A_2") (pintype "passive"))
      (node (ref "D9") (pin "2") (pinfunction "A_2") (pintype "passive"))
      (node (ref "J9") (pin "9") (pinfunction "VCC_9") (pintype "power_in"))
      (node (ref "R259") (pin "2") (pinfunction "2_2") (pintype "passive"))
      (node (ref "R260") (pin "2") (pinfunction "2_2") (pintype "passive"))
      (node (ref "R261") (pin "2") (pinfunction "2_2") (pintype "passive"))
      (node (ref "R262") (pin "1") (pinfunction "1_1") (pintype "passive"))
      (node (ref "R263") (pin "2") (pinfunction "2_2") (pintype "passive"))
      (node (ref "U17") (pin "A11") (pinfunction "VDDO_A11") (pintype "power_in"))
      (node (ref "U17") (pin "A19") (pinfunction "AVDD_A19") (pintype "power_in"))
      (node (ref "U17") (pin "A24") (pinfunction "AVDD_A24") (pintype "power_in"))
      (node (ref "U17") (pin "A3") (pinfunction "VDDO_A3") (pintype "power_in"))
      (node (ref "U17") (pin "A34") (pinfunction "CONFIG[2]_A34") (pintype "input"))
      (node (ref "U17") (pin "A52") (pinfunction "VDDO_A52") (pintype "power_in"))
      (node (ref "U17") (pin "B12") (pinfunction "VDDOX_B12") (pintype "power_in"))
      (node (ref "U17") (pin "B15") (pinfunction "AVDD_B15") (pintype "power_in"))
      (node (ref "U17") (pin "B17") (pinfunction "AVDD_B17") (pintype "power_in"))
      (node (ref "U17") (pin "B19") (pinfunction "AVDD_B19") (pintype "power_in"))
      (node (ref "U17") (pin "B23") (pinfunction "VDDOX_B23") (pintype "power_in"))
      (node (ref "U17") (pin "B24") (pinfunction "VDDOH_B24") (pintype "power_in"))
      (node (ref "U17") (pin "B31") (pinfunction "VDDOH_B31") (pintype "power_in"))
      (node (ref "U17") (pin "B34") (pinfunction "VDDOH_B34") (pintype "power_in"))
      (node (ref "U17") (pin "B36") (pinfunction "AVDD_B36") (pintype "power_in"))
      (node (ref "U17") (pin "B41") (pinfunction "VDDO_B41") (pintype "power_in"))
      (node (ref "U18") (pin "4") (pinfunction "VCC_4") (pintype "power_in"))
      (node (ref "U19") (pin "3") (pinfunction "IN_3") (pintype "power_in"))
      (node (ref "U19") (pin "6") (pinfunction "~{SHDN}_6") (pintype "input"))
    )
    (net (code "33") (name "IO_5V") (class "Default")
      (node (ref "C327") (pin "2") (pinfunction "2_2") (pintype "passive"))
      (node (ref "U19") (pin "1") (pinfunction "BIAS_1") (pintype "power_in"))
    )
    (net (code "34") (name "Net-(C310-Pad1)") (class "Default")
      (node (ref "C310") (pin "1") (pinfunction "1_1") (pintype "passive"))
      (node (ref "R249") (pin "2") (pinfunction "2_2") (pintype "passive"))
      (node (ref "R250") (pin "2") (pinfunction "2_2") (pintype "passive"))
    )
    (net (code "35") (name "Net-(C311-Pad1)") (class "Default")
      (node (ref "C311") (pin "1") (pinfunction "1_1") (pintype "passive"))
      (node (ref "R251") (pin "2") (pinfunction "2_2") (pintype "passive"))
      (node (ref "R252") (pin "2") (pinfunction "2_2") (pintype "passive"))
    )
    (net (code "36") (name "Net-(C312-Pad1)") (class "Default")
      (node (ref "C312") (pin "1") (pinfunction "1_1") (pintype "passive"))
      (node (ref "R253") (pin "2") (pinfunction "2_2") (pintype "passive"))
      (node (ref "R254") (pin "2") (pinfunction "2_2") (pintype "passive"))
    )
    (net (code "37") (name "Net-(C314-Pad1)") (class "Default")
      (node (ref "C314") (pin "1") (pinfunction "1_1") (pintype "passive"))
      (node (ref "R255") (pin "2") (pinfunction "2_2") (pintype "passive"))
      (node (ref "R256") (pin "2") (pinfunction "2_2") (pintype "passive"))
    )
    (net (code "38") (name "Net-(D5-K)") (class "Default")
      (node (ref "D5") (pin "1") (pinfunction "K_1") (pintype "passive"))
      (node (ref "R266") (pin "1") (pinfunction "1_1") (pintype "passive"))
    )
    (net (code "39") (name "Net-(D6-K)") (class "Default")
      (node (ref "D6") (pin "1") (pinfunction "K_1") (pintype "passive"))
      (node (ref "R267") (pin "1") (pinfunction "1_1") (pintype "passive"))
    )
    (net (code "40") (name "Net-(D7-K)") (class "Default")
      (node (ref "D7") (pin "1") (pinfunction "K_1") (pintype "passive"))
      (node (ref "R268") (pin "1") (pinfunction "1_1") (pintype "passive"))
    )
    (net (code "41") (name "Net-(D8-K)") (class "Default")
      (node (ref "D8") (pin "1") (pinfunction "K_1") (pintype "passive"))
      (node (ref "R269") (pin "1") (pinfunction "1_1") (pintype "passive"))
    )
    (net (code "42") (name "Net-(D9-K)") (class "Default")
      (node (ref "D9") (pin "1") (pinfunction "K_1") (pintype "passive"))
      (node (ref "R271") (pin "1") (pinfunction "1_1") (pintype "passive"))
    )
    (net (code "43") (name "Net-(U17A-RSET)") (class "Default")
      (node (ref "R265") (pin "1") (pinfunction "1_1") (pintype "passive"))
      (node (ref "U17") (pin "B14") (pinfunction "RSET_B14") (pintype "input"))
    )
    (net (code "44") (name "Net-(U17A-TRSTn)") (class "Default")
      (node (ref "R264") (pin "1") (pinfunction "1_1") (pintype "passive"))
      (node (ref "U17") (pin "A25") (pinfunction "TRSTn_A25") (pintype "input"))
    )
    (net (code "45") (name "Net-(U17A-TXD0{slash}TD0)") (class "Default")
      (node (ref "R257") (pin "2") (pinfunction "2_2") (pintype "passive"))
      (node (ref "U17") (pin "A6") (pinfunction "TXD0/TD0_A6") (pintype "input"))
      (node (ref "U17") (pin "B6") (pinfunction "TXD1/TD1_B6") (pintype "input"))
      (node (ref "U17") (pin "B7") (pinfunction "TXD2/TD2_B7") (pintype "input"))
      (node (ref "U17") (pin "B8") (pinfunction "TXD3/TD3_B8") (pintype "input"))
    )
    (net (code "46") (name "Net-(U17A-TXD4)") (class "Default")
      (node (ref "R258") (pin "2") (pinfunction "2_2") (pintype "passive"))
      (node (ref "U17") (pin "A10") (pinfunction "TXD6_A10") (pintype "input"))
      (node (ref "U17") (pin "A9") (pinfunction "TXD4_A9") (pintype "input"))
      (node (ref "U17") (pin "B10") (pinfunction "TXD7_B10") (pintype "input"))
      (node (ref "U17") (pin "B9") (pinfunction "TXD5_B9") (pintype "input"))
    )
    (net (code "47") (name "Net-(U17A-XTAL1)") (class "Default")
      (node (ref "U17") (pin "A30") (pinfunction "XTAL1_A30") (pintype "input"))
      (node (ref "U18") (pin "3") (pinfunction "OUTPUT_3") (pintype "passive"))
    )
    (net (code "48") (name "Net-(U18-TRI-STATE)") (class "Default")
      (node (ref "R262") (pin "2") (pinfunction "2_2") (pintype "passive"))
      (node (ref "U18") (pin "1") (pinfunction "TRI-STATE_1") (pintype "passive"))
    )
    (net (code "49") (name "Net-(U19-ADJ)") (class "Default")
      (node (ref "R270") (pin "1") (pinfunction "1_1") (pintype "passive"))
      (node (ref "R272") (pin "2") (pinfunction "2_2") (pintype "passive"))
      (node (ref "U19") (pin "5") (pinfunction "ADJ_5") (pintype "input"))
    )
    (net (code "50") (name "unconnected-(U17A-125CLK-PadB11)") (class "Default")
      (node (ref "U17") (pin "B11") (pinfunction "125CLK_B11") (pintype "output"))
    )
    (net (code "51") (name "unconnected-(U17A-COL{slash}LPBK-PadA45)") (class "Default")
      (node (ref "U17") (pin "A45") (pinfunction "COL/LPBK_A45") (pintype "bidirectional"))
    )
    (net (code "52") (name "unconnected-(U17A-CRS{slash}COMMA-PadB39)") (class "Default")
      (node (ref "U17") (pin "B39") (pinfunction "CRS/COMMA_B39") (pintype "tri_state"))
    )
    (net (code "53") (name "unconnected-(U17A-GTX_CLK{slash}TBI_TXCLK{slash}TXC-PadB4)") (class "Default")
      (node (ref "U17") (pin "B4") (pinfunction "GTX_CLK/TBI_TXCLK/TXC_B4") (pintype "input"))
    )
    (net (code "54") (name "unconnected-(U17A-HSDAC+-PadA20)") (class "Default")
      (node (ref "U17") (pin "A20") (pinfunction "HSDAC+_A20") (pintype "passive"))
    )
    (net (code "55") (name "unconnected-(U17A-HSDAC--PadB18)") (class "Default")
      (node (ref "U17") (pin "B18") (pinfunction "HSDAC-_B18") (pintype "passive"))
    )
    (net (code "56") (name "unconnected-(U17A-LED_DUPLEX-PadB33)") (class "Default")
      (node (ref "U17") (pin "B33") (pinfunction "LED_DUPLEX_B33") (pintype "output"))
    )
    (net (code "57") (name "unconnected-(U17A-NC-PadA7)") (class "Default")
      (node (ref "U17") (pin "A7") (pinfunction "NC_A7") (pintype "passive"))
    )
    (net (code "58") (name "unconnected-(U17A-NC-PadA28)") (class "Default")
      (node (ref "U17") (pin "A28") (pinfunction "NC_A28") (pintype "passive"))
    )
    (net (code "59") (name "unconnected-(U17A-RXD0{slash}RD0-PadA51)") (class "Default")
      (node (ref "U17") (pin "A51") (pinfunction "RXD0/RD0_A51") (pintype "tri_state"))
    )
    (net (code "60") (name "unconnected-(U17A-RXD1{slash}RD1-PadB43)") (class "Default")
      (node (ref "U17") (pin "B43") (pinfunction "RXD1/RD1_B43") (pintype "tri_state"))
    )
    (net (code "61") (name "unconnected-(U17A-RXD2{slash}RD2-PadA50)") (class "Default")
      (node (ref "U17") (pin "A50") (pinfunction "RXD2/RD2_A50") (pintype "tri_state"))
    )
    (net (code "62") (name "unconnected-(U17A-RXD3{slash}RD3-PadA49)") (class "Default")
      (node (ref "U17") (pin "A49") (pinfunction "RXD3/RD3_A49") (pintype "tri_state"))
    )
    (net (code "63") (name "unconnected-(U17A-RXD4-PadB42)") (class "Default")
      (node (ref "U17") (pin "B42") (pinfunction "RXD4_B42") (pintype "tri_state"))
    )
    (net (code "64") (name "unconnected-(U17A-RXD5-PadA48)") (class "Default")
      (node (ref "U17") (pin "A48") (pinfunction "RXD5_A48") (pintype "tri_state"))
    )
    (net (code "65") (name "unconnected-(U17A-RXD6-PadA47)") (class "Default")
      (node (ref "U17") (pin "A47") (pinfunction "RXD6_A47") (pintype "tri_state"))
    )
    (net (code "66") (name "unconnected-(U17A-RXD7-PadB40)") (class "Default")
      (node (ref "U17") (pin "B40") (pinfunction "RXD7_B40") (pintype "tri_state"))
    )
    (net (code "67") (name "unconnected-(U17A-RX_CLK{slash}RCLK0{slash}RXC-PadB1)") (class "Default")
      (node (ref "U17") (pin "B1") (pinfunction "RX_CLK/RCLK0/RXC_B1") (pintype "tri_state"))
    )
    (net (code "68") (name "unconnected-(U17A-RX_DV{slash}RXD8{slash}RX_CTL{slash}RD4_RD9-PadB44)") (class "Default")
      (node (ref "U17") (pin "B44") (pinfunction "RX_DV/RXD8/RX_CTL/RD4_RD9_B44") (pintype "tri_state"))
    )
    (net (code "69") (name "unconnected-(U17A-RX_ER{slash}RXD9-PadA2)") (class "Default")
      (node (ref "U17") (pin "A2") (pinfunction "RX_ER/RXD9_A2") (pintype "tri_state"))
    )
    (net (code "70") (name "unconnected-(U17A-SEL_FREQ-PadB26)") (class "Default")
      (node (ref "U17") (pin "B26") (pinfunction "SEL_FREQ_B26") (pintype "input"))
    )
    (net (code "71") (name "unconnected-(U17A-S_CLK+{slash}SD+-PadA43)") (class "Default")
      (node (ref "U17") (pin "A43") (pinfunction "S_CLK+/SD+_A43") (pintype "bidirectional"))
    )
    (net (code "72") (name "unconnected-(U17A-S_CLK-{slash}SD--PadB37)") (class "Default")
      (node (ref "U17") (pin "B37") (pinfunction "S_CLK-/SD-_B37") (pintype "bidirectional"))
    )
    (net (code "73") (name "unconnected-(U17A-TCK-PadA26)") (class "Default")
      (node (ref "U17") (pin "A26") (pinfunction "TCK_A26") (pintype "input"))
    )
    (net (code "74") (name "unconnected-(U17A-TDI-PadB21)") (class "Default")
      (node (ref "U17") (pin "B21") (pinfunction "TDI_B21") (pintype "input"))
    )
    (net (code "75") (name "unconnected-(U17A-TDO-PadA27)") (class "Default")
      (node (ref "U17") (pin "A27") (pinfunction "TDO_A27") (pintype "output"))
    )
    (net (code "76") (name "unconnected-(U17A-TMS-PadB22)") (class "Default")
      (node (ref "U17") (pin "B22") (pinfunction "TMS_B22") (pintype "input"))
    )
    (net (code "77") (name "unconnected-(U17A-TX_CLK{slash}RCLK1-PadB2)") (class "Default")
      (node (ref "U17") (pin "B2") (pinfunction "TX_CLK/RCLK1_B2") (pintype "tri_state"))
    )
    (net (code "78") (name "unconnected-(U17A-TX_EN{slash}TXD8{slash}TX_CTL{slash}TD4_TD9-PadA5)") (class "Default")
      (node (ref "U17") (pin "A5") (pinfunction "TX_EN/TXD8/TX_CTL/TD4_TD9_A5") (pintype "input"))
    )
    (net (code "79") (name "unconnected-(U17A-TX_ER{slash}TXD9-PadA4)") (class "Default")
      (node (ref "U17") (pin "A4") (pinfunction "TX_ER/TXD9_A4") (pintype "input"))
    )
    (net (code "80") (name "unconnected-(U17A-XTAL2-PadB25)") (class "Default")
      (node (ref "U17") (pin "B25") (pinfunction "XTAL2_B25") (pintype "passive"))
    )
  )
)
